# Sheet5.net
KiCad netlist of a schematic drawn in Altium Designer
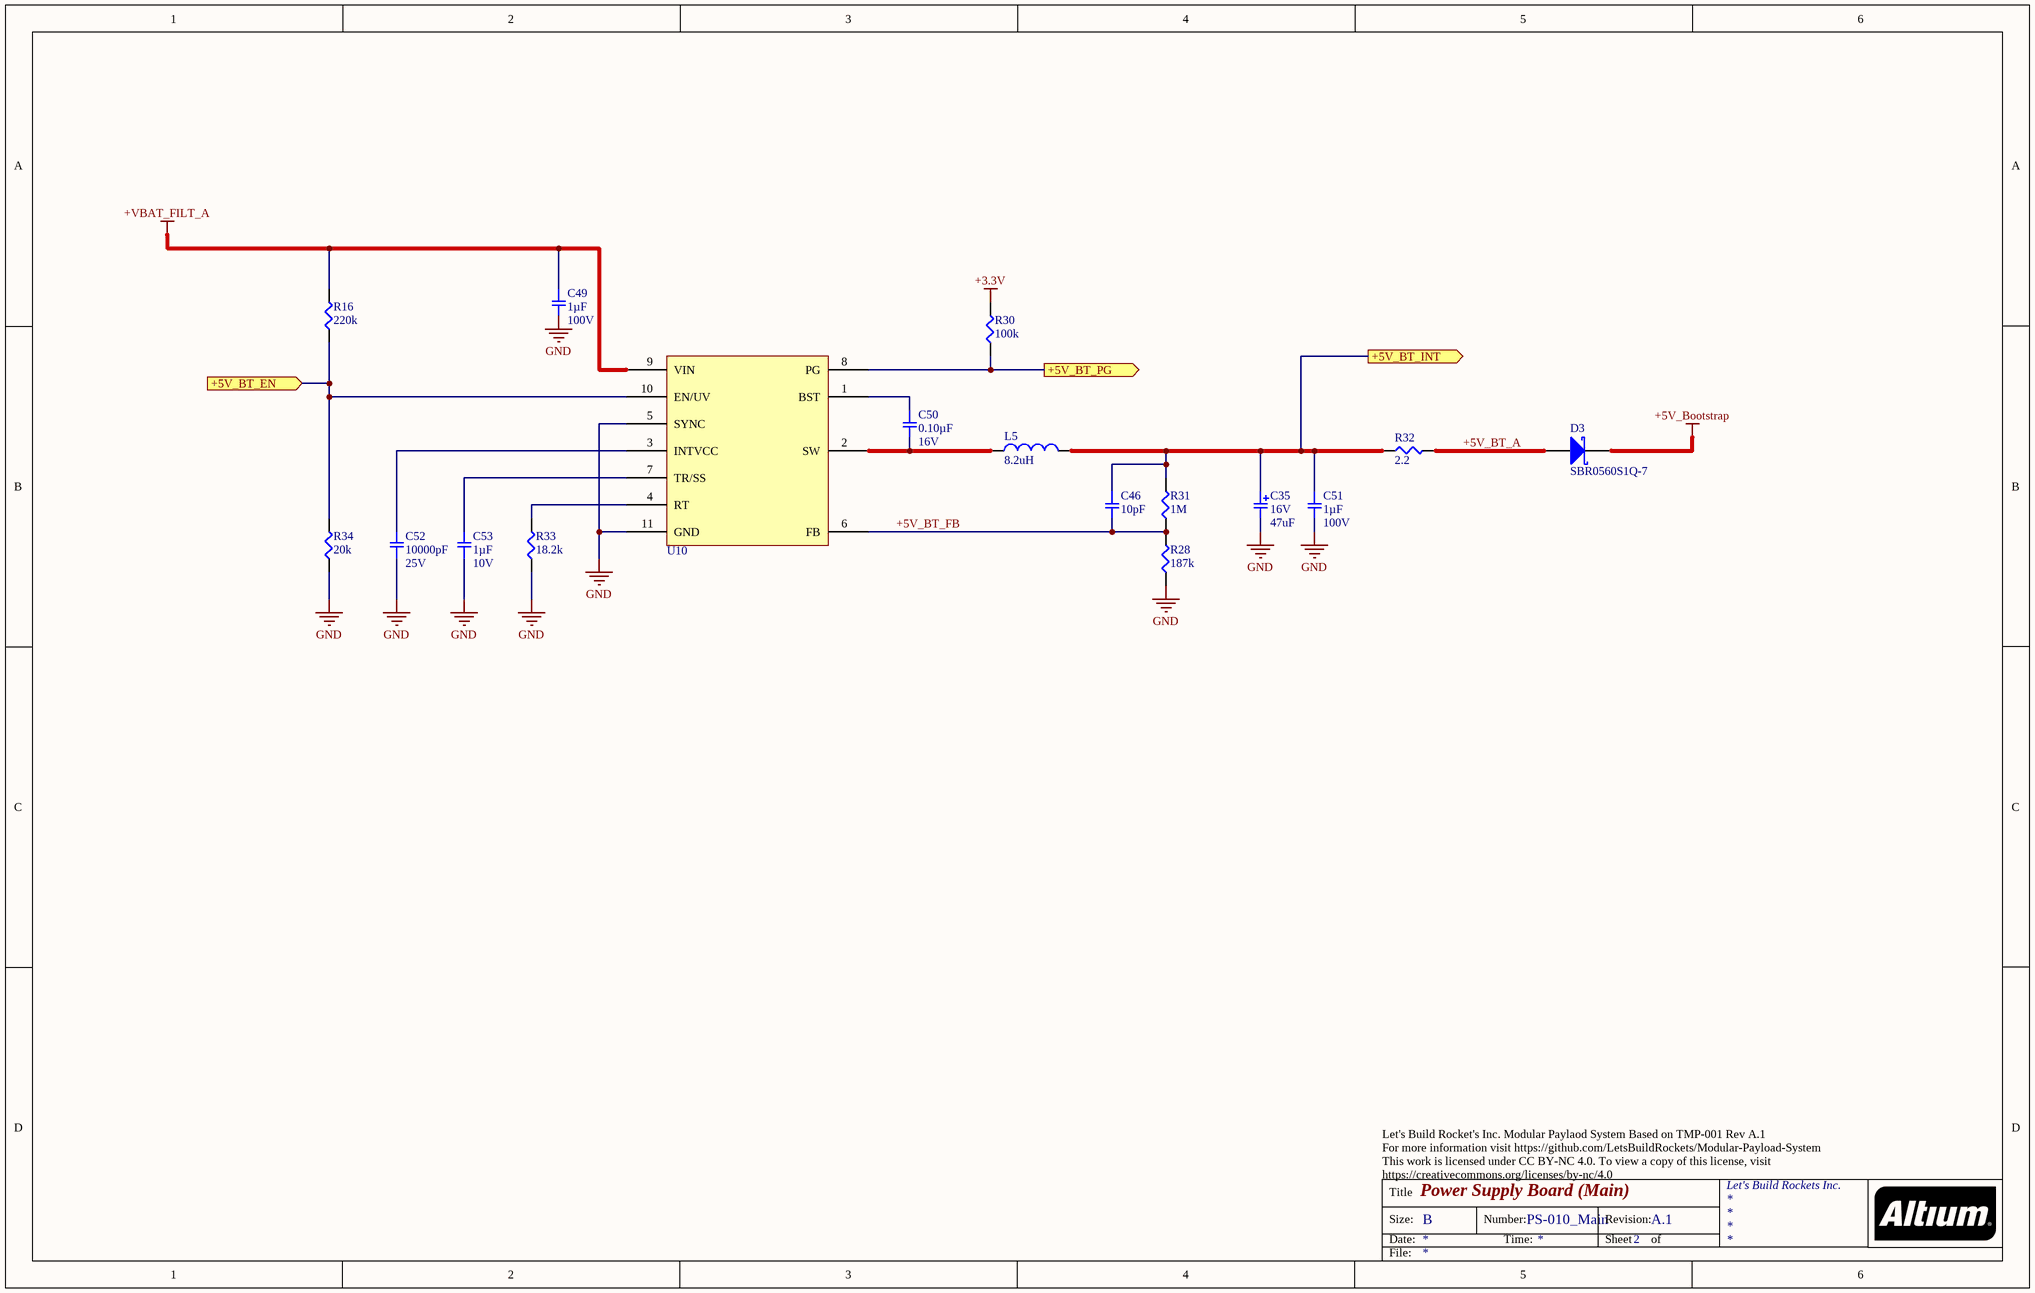
[diagram p0: Sheet5.SchDoc]

(export (version "E")
  (design (tool "Eeschema 10.0.6"))
  (components
    (comp (ref "C35")
      (value "47uF")
      (footprint "KEMET W - CAPMP7343X15N")
      (fields (field (name "VOLTAGE") "16V") (field (name "Comment") "T521W476M016ATE045"))
      (libsource (lib "KEMET") (part "T521W476M016ATE045"))
    )
    (comp (ref "C46")
      (value "10pF")
      (footprint "SMD-0402C")
      (description "CAP CER 10PF 50V NP0 0402")
      (fields
        (field (name "DIGI-KEY PART NUMBER") "490-10668-1-ND")
        (field (name "PART NUMBER") "GCM1555C1H100JA16D")
      )
      (libsource (lib "capacitor_murata_0402") (part "GCM1555C1H100JA16D"))
    )
    (comp (ref "C49")
      (value "1µF")
      (footprint "SMD-0805C")
      (description "CAP CER 1UF 100V X7S 0805")
      (fields
        (field (name "DIGI-KEY PART NUMBER") "490-10918-1-ND")
        (field (name "PART NUMBER") "GRJ21BC72A105KE11L")
        (field (name "VOLTAGE") "100V")
      )
      (libsource (lib "capacitor_murata_0805") (part "GRJ21BC72A105KE11L"))
    )
    (comp (ref "C50")
      (value "0.10µF")
      (footprint "SMD-0402C")
      (description "CAP CER 0.1UF 16V X7R 0402")
      (fields
        (field (name "DIGI-KEY PART NUMBER") "490-4759-1-ND")
        (field (name "PART NUMBER") "GCM155R71C104KA55D")
        (field (name "VOLTAGE") "16V")
      )
      (libsource (lib "capacitor_murata_0402") (part "GCM155R71C104KA55D"))
    )
    (comp (ref "C51")
      (value "1µF")
      (footprint "SMD-0805C")
      (description "CAP CER 1UF 100V X7S 0805")
      (fields
        (field (name "DIGI-KEY PART NUMBER") "490-10918-1-ND")
        (field (name "PART NUMBER") "GRJ21BC72A105KE11L")
        (field (name "VOLTAGE") "100V")
      )
      (libsource (lib "capacitor_murata_0805") (part "GRJ21BC72A105KE11L"))
    )
    (comp (ref "C52")
      (value "10000pF")
      (footprint "SMD-0402C")
      (description "CAP CER 10000PF 25V X7R 0402")
      (fields
        (field (name "DIGI-KEY PART NUMBER") "490-6043-1-ND")
        (field (name "PART NUMBER") "GCM155R71E103KA37D")
        (field (name "VOLTAGE") "25V")
      )
      (libsource (lib "capacitor_murata_0402") (part "GCM155R71E103KA37D"))
    )
    (comp (ref "C53")
      (value "1µF")
      (footprint "SMD-0402C")
      (description "CAP CER 1UF 10V X7S 0402")
      (fields
        (field (name "DIGI-KEY PART NUMBER") "490-13409-1-ND")
        (field (name "PART NUMBER") "GCM155C71A105KE38D")
        (field (name "VOLTAGE") "10V")
      )
      (libsource (lib "capacitor_murata_0402") (part "GCM155C71A105KE38D"))
    )
    (comp (ref "D3")
      (value "SBR0560S1Q-7")
      (footprint "SOD123")
      (libsource (lib "ModularPayload") (part "SBR0560S1Q-7"))
    )
    (comp (ref "L5")
      (value "8.2uH")
      (footprint "INDM4040X21N (XGL4020)")
      (fields (field (name "Comment") "XGL4020-882ME"))
      (libsource (lib "ModularPayload") (part "XGL4020-882ME"))
    )
    (comp (ref "R16")
      (value "220k")
      (footprint "SMD-0402-RES")
      (description "RES SMD 220K OHM 1% 1/10W 0402")
      (fields
        (field (name "PART NUMBER") "ERJ-2RKF2203X")
        (field (name "DIGI-KEY PART NUMBER") "P220KLCT-ND")
      )
      (libsource (lib "Panasonic_ERJ_0402") (part "ERJ-2RKF2203X"))
    )
    (comp (ref "R28")
      (value "187k")
      (footprint "SMD-0603-RES")
      (description "RES SMD 187K OHM 1% 1/10W 0603")
      (fields
        (field (name "PART NUMBER") "ERJ-3EKF1873V")
        (field (name "DIGI-KEY PART NUMBER") "P187KHCT-ND")
      )
      (libsource (lib "Panasonic_ERJ_0603") (part "ERJ-3EKF1873V"))
    )
    (comp (ref "R30")
      (value "100k")
      (footprint "SMD-0402-RES")
      (description "RES SMD 100K OHM 5% 1/10W 0402")
      (fields (field (name "PART NUMBER") "ERJ-2GEJ104X") (field (name "DIGI-KEY PART NUMBER") "P100KJCT-ND"))
      (libsource (lib "Panasonic_ERJ_0402") (part "ERJ-2GEJ104X"))
    )
    (comp (ref "R31")
      (value "1M")
      (footprint "SMD-0603-RES")
      (description "RES SMD 1M OHM 1% 1/10W 0603")
      (fields
        (field (name "PART NUMBER") "ERJ-3EKF1004V")
        (field (name "DIGI-KEY PART NUMBER") "P1.00MHCT-ND")
      )
      (libsource (lib "Panasonic_ERJ_0603") (part "ERJ-3EKF1004V"))
    )
    (comp (ref "R32")
      (value "2.2")
      (footprint "SMD-0805-RES")
      (description "RES SMD 2.2 OHM 5% 1/8W 0805")
      (fields (field (name "PART NUMBER") "ERJ-6GEYJ2R2V") (field (name "DIGI-KEY PART NUMBER") "P2.2ACT-ND"))
      (libsource (lib "Panasonic_ERJ_0805") (part "ERJ-6GEYJ2R2V"))
    )
    (comp (ref "R33")
      (value "18.2k")
      (footprint "SMD-0402-RES")
      (description "RES SMD 18.2K OHM 1% 1/10W 0402")
      (fields
        (field (name "PART NUMBER") "ERJ-2RKF1822X")
        (field (name "DIGI-KEY PART NUMBER") "P18.2KLCT-ND")
      )
      (libsource (lib "Panasonic_ERJ_0402") (part "ERJ-2RKF1822X"))
    )
    (comp (ref "R34")
      (value "20k")
      (footprint "SMD-0402-RES")
      (description "RES SMD 20K OHM 1% 1/10W 0402")
      (fields
        (field (name "PART NUMBER") "ERJ-2RKF2002X")
        (field (name "DIGI-KEY PART NUMBER") "P20.0KLCT-ND")
      )
      (libsource (lib "Panasonic_ERJ_0402") (part "ERJ-2RKF2002X"))
    )
    (comp (ref "U10")
      (value "LT8606*MSE")
      (footprint "TSSOP50P490X110_HS-11N (LT8606MSE)")
      (libsource (lib "ModularPayload") (part "LT8606*MSE"))
    )
  )
  (nets
    (net (code "1") (name "+3.3V") (class "Default")
      (node (ref "R30") (pin "2") (pinfunction "2_2") (pintype "passive"))
    )
    (net (code "2") (name "+5V_Bootstrap") (class "Default")
      (node (ref "D3") (pin "K") (pinfunction "K_K") (pintype "passive"))
    )
    (net (code "3") (name "+VBAT_FILT_A") (class "Default")
      (node (ref "C49") (pin "1") (pinfunction "1_1") (pintype "passive"))
      (node (ref "R16") (pin "2") (pinfunction "2_2") (pintype "passive"))
      (node (ref "U10") (pin "9") (pinfunction "VIN_9") (pintype "passive"))
    )
    (net (code "4") (name "/+5V_BT_A") (class "Default")
      (node (ref "D3") (pin "A") (pinfunction "A_A") (pintype "passive"))
      (node (ref "R32") (pin "2") (pinfunction "2_2") (pintype "passive"))
    )
    (net (code "5") (name "/+5V_BT_EN") (class "Default")
      (node (ref "R16") (pin "1") (pinfunction "1_1") (pintype "passive"))
      (node (ref "R34") (pin "2") (pinfunction "2_2") (pintype "passive"))
      (node (ref "U10") (pin "10") (pinfunction "EN/UV_10") (pintype "passive"))
    )
    (net (code "6") (name "/+5V_BT_FB") (class "Default")
      (node (ref "C46") (pin "2") (pinfunction "2_2") (pintype "passive"))
      (node (ref "R28") (pin "2") (pinfunction "2_2") (pintype "passive"))
      (node (ref "R31") (pin "1") (pinfunction "1_1") (pintype "passive"))
      (node (ref "U10") (pin "6") (pinfunction "FB_6") (pintype "passive"))
    )
    (net (code "7") (name "/+5V_BT_INT") (class "Default")
      (node (ref "C35") (pin "1") (pinfunction "1_1") (pintype "passive"))
      (node (ref "C46") (pin "1") (pinfunction "1_1") (pintype "passive"))
      (node (ref "C51") (pin "1") (pinfunction "1_1") (pintype "passive"))
      (node (ref "L5") (pin "2") (pinfunction "2_2") (pintype "passive"))
      (node (ref "R31") (pin "2") (pinfunction "2_2") (pintype "passive"))
      (node (ref "R32") (pin "1") (pinfunction "1_1") (pintype "passive"))
    )
    (net (code "8") (name "/+5V_BT_PG") (class "Default")
      (node (ref "R30") (pin "1") (pinfunction "1_1") (pintype "passive"))
      (node (ref "U10") (pin "8") (pinfunction "PG_8") (pintype "passive"))
    )
    (net (code "9") (name "GND") (class "Default")
      (node (ref "C35") (pin "2") (pinfunction "2_2") (pintype "passive"))
      (node (ref "C49") (pin "2") (pinfunction "2_2") (pintype "passive"))
      (node (ref "C51") (pin "2") (pinfunction "2_2") (pintype "passive"))
      (node (ref "C52") (pin "1") (pinfunction "1_1") (pintype "passive"))
      (node (ref "C53") (pin "1") (pinfunction "1_1") (pintype "passive"))
      (node (ref "R28") (pin "1") (pinfunction "1_1") (pintype "passive"))
      (node (ref "R33") (pin "1") (pinfunction "1_1") (pintype "passive"))
      (node (ref "R34") (pin "1") (pinfunction "1_1") (pintype "passive"))
      (node (ref "U10") (pin "11") (pinfunction "GND_11") (pintype "passive"))
      (node (ref "U10") (pin "5") (pinfunction "SYNC_5") (pintype "passive"))
    )
    (net (code "10") (name "Net-(U10-BST)") (class "Default")
      (node (ref "C50") (pin "1") (pinfunction "1_1") (pintype "passive"))
      (node (ref "U10") (pin "1") (pinfunction "BST_1") (pintype "passive"))
    )
    (net (code "11") (name "Net-(U10-INTVCC)") (class "Default")
      (node (ref "C52") (pin "2") (pinfunction "2_2") (pintype "passive"))
      (node (ref "U10") (pin "3") (pinfunction "INTVCC_3") (pintype "passive"))
    )
    (net (code "12") (name "Net-(U10-RT)") (class "Default")
      (node (ref "R33") (pin "2") (pinfunction "2_2") (pintype "passive"))
      (node (ref "U10") (pin "4") (pinfunction "RT_4") (pintype "passive"))
    )
    (net (code "13") (name "Net-(U10-SW)") (class "Default")
      (node (ref "C50") (pin "2") (pinfunction "2_2") (pintype "passive"))
      (node (ref "L5") (pin "1") (pinfunction "1_1") (pintype "passive"))
      (node (ref "U10") (pin "2") (pinfunction "SW_2") (pintype "passive"))
    )
    (net (code "14") (name "Net-(U10-TR{slash}SS)") (class "Default")
      (node (ref "C53") (pin "2") (pinfunction "2_2") (pintype "passive"))
      (node (ref "U10") (pin "7") (pinfunction "TR/SS_7") (pintype "passive"))
    )
  )
)
